# Super-Regenerative-Airband-1Transistor-K.net
KiCad netlist of a schematic drawn in EAGLE
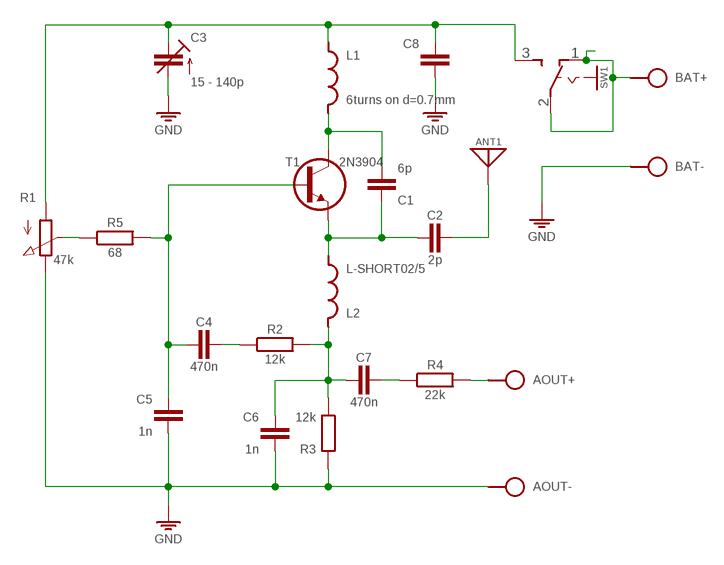
[diagram p0: schematic, sheet 1]

(export (version "E")
  (design (tool "Eeschema 10.0.6"))
  (components
    (comp (ref "ANT1")
      (value "ANT")
      (footprint "eagle-import:SPAD")
      (libsource (lib "eagle-import") (part "ANT"))
    )
    (comp (ref "AOUT+")
      (value "SPAD")
      (footprint "eagle-import:SPAD")
      (libsource (lib "eagle-import") (part "SPAD"))
    )
    (comp (ref "AOUT-")
      (value "SPAD")
      (footprint "eagle-import:SPAD")
      (libsource (lib "eagle-import") (part "SPAD"))
    )
    (comp (ref "BAT+")
      (value "SPAD")
      (footprint "eagle-import:SPAD")
      (libsource (lib "eagle-import") (part "SPAD"))
    )
    (comp (ref "BAT-")
      (value "SPAD")
      (footprint "eagle-import:SPAD")
      (libsource (lib "eagle-import") (part "SPAD"))
    )
    (comp (ref "C1")
      (value "6p")
      (footprint "eagle-import:C050-020X036")
      (libsource (lib "eagle-import") (part "C050-020X036"))
    )
    (comp (ref "C2")
      (value "2p")
      (footprint "eagle-import:C025-015X024")
      (libsource (lib "eagle-import") (part "C025-015X024"))
    )
    (comp (ref "C3")
      (value "15 - 140p")
      (footprint "eagle-import:TRIM-2222-808")
      (libsource (lib "eagle-import") (part "C-TR-PH201272222-808-2PINB"))
    )
    (comp (ref "C4")
      (value "470n")
      (footprint "eagle-import:C050-020X036")
      (libsource (lib "eagle-import") (part "C050-020X036"))
    )
    (comp (ref "C5")
      (value "1n")
      (footprint "eagle-import:C025-020X036")
      (libsource (lib "eagle-import") (part "C025-020X036"))
    )
    (comp (ref "C6")
      (value "1n")
      (footprint "eagle-import:C050-020X036")
      (libsource (lib "eagle-import") (part "C050-020X036"))
    )
    (comp (ref "C7")
      (value "470n")
      (footprint "eagle-import:C050-020X036")
      (libsource (lib "eagle-import") (part "C050-020X036"))
    )
    (comp (ref "C8")
      (value "C050-025X075")
      (footprint "eagle-import:C050-025X075")
      (libsource (lib "eagle-import") (part "C050-025X075"))
    )
    (comp (ref "L1")
      (value "6turns on d=0.7mm")
      (footprint "eagle-import:L-04_7V-X")
      (libsource (lib "eagle-import") (part "L-SHORTL-04/7V-X"))
    )
    (comp (ref "L2")
      (value "L-SHORT02/5")
      (footprint "eagle-import:L-04-5_5V")
      (libsource (lib "eagle-import") (part "L-SHORT04-5/5V"))
    )
    (comp (ref "R1")
      (value "47k")
      (footprint "eagle-import:POT")
      (libsource (lib "eagle-import") (part "POT"))
    )
    (comp (ref "R2")
      (value "12k")
      (footprint "eagle-import:0202_7")
      (libsource (lib "eagle-import") (part "R-H0202/7"))
    )
    (comp (ref "R3")
      (value "12k")
      (footprint "eagle-import:0202_7")
      (libsource (lib "eagle-import") (part "R0202/7"))
    )
    (comp (ref "R4")
      (value "22k")
      (footprint "eagle-import:0202_7")
      (libsource (lib "eagle-import") (part "R-H0202/7"))
    )
    (comp (ref "R5")
      (value "68")
      (footprint "eagle-import:0202_7")
      (libsource (lib "eagle-import") (part "R-H0202/7"))
    )
    (comp (ref "SW1")
      (value "SL-SW-1P-2T-H")
      (footprint "eagle-import:SLSW-1P2T-H")
      (libsource (lib "eagle-import") (part "SL-SW-1P-2T-H"))
    )
    (comp (ref "T1")
      (value "2N3904")
      (footprint "eagle-import:TO92")
      (libsource (lib "eagle-import") (part "2N3904"))
    )
  )
  (nets
    (net (code "1") (name "GND") (class "Default")
      (node (ref "AOUT-") (pin "1") (pinfunction "P$1_1") (pintype "bidirectional"))
      (node (ref "BAT-") (pin "1") (pinfunction "P$1_1") (pintype "bidirectional"))
      (node (ref "C3") (pin "2") (pinfunction "A_2") (pintype "passive"))
      (node (ref "C5") (pin "2") (pinfunction "2_2") (pintype "passive"))
      (node (ref "C6") (pin "2") (pinfunction "2_2") (pintype "passive"))
      (node (ref "C8") (pin "2") (pinfunction "2_2") (pintype "passive"))
      (node (ref "R1") (pin "3") (pinfunction "E_3") (pintype "passive"))
      (node (ref "R3") (pin "2") (pinfunction "2_2") (pintype "passive"))
    )
    (net (code "2") (name "Net-(ANT1-Pad1)") (class "Default")
      (node (ref "ANT1") (pin "1") (pinfunction "1_1") (pintype "output"))
      (node (ref "C2") (pin "1") (pinfunction "1_1") (pintype "passive"))
    )
    (net (code "3") (name "Net-(AOUT+-P$1)") (class "Default")
      (node (ref "AOUT+") (pin "1") (pinfunction "P$1_1") (pintype "bidirectional"))
      (node (ref "R4") (pin "2") (pinfunction "2_2") (pintype "passive"))
    )
    (net (code "4") (name "Net-(BAT+-P$1)") (class "Default")
      (node (ref "BAT+") (pin "1") (pinfunction "P$1_1") (pintype "bidirectional"))
      (node (ref "SW1") (pin "1") (pinfunction "O_1") (pintype "passive"))
      (node (ref "SW1") (pin "2") (pinfunction "P_2") (pintype "passive"))
    )
    (net (code "5") (name "Net-(C3-E)") (class "Default")
      (node (ref "C3") (pin "3") (pinfunction "E_3") (pintype "passive"))
      (node (ref "C8") (pin "1") (pinfunction "1_1") (pintype "passive"))
      (node (ref "L1") (pin "2") (pinfunction "2_2") (pintype "passive"))
      (node (ref "R1") (pin "1") (pinfunction "A_1") (pintype "passive"))
      (node (ref "SW1") (pin "3") (pinfunction "S_3") (pintype "passive"))
    )
    (net (code "6") (name "Net-(C4-Pad1)") (class "Default")
      (node (ref "C4") (pin "1") (pinfunction "1_1") (pintype "passive"))
      (node (ref "R2") (pin "1") (pinfunction "1_1") (pintype "passive"))
    )
    (net (code "7") (name "Net-(C6-Pad1)") (class "Default")
      (node (ref "C6") (pin "1") (pinfunction "1_1") (pintype "passive"))
      (node (ref "C7") (pin "2") (pinfunction "2_2") (pintype "passive"))
      (node (ref "L2") (pin "2") (pinfunction "2_2") (pintype "passive"))
      (node (ref "R2") (pin "2") (pinfunction "2_2") (pintype "passive"))
      (node (ref "R3") (pin "1") (pinfunction "1_1") (pintype "passive"))
    )
    (net (code "8") (name "Net-(C7-Pad1)") (class "Default")
      (node (ref "C7") (pin "1") (pinfunction "1_1") (pintype "passive"))
      (node (ref "R4") (pin "1") (pinfunction "1_1") (pintype "passive"))
    )
    (net (code "9") (name "Net-(R1-S)") (class "Default")
      (node (ref "R1") (pin "2") (pinfunction "S_2") (pintype "passive"))
      (node (ref "R5") (pin "1") (pinfunction "1_1") (pintype "passive"))
    )
    (net (code "10") (name "Net-(T1-B)") (class "Default")
      (node (ref "C4") (pin "2") (pinfunction "2_2") (pintype "passive"))
      (node (ref "C5") (pin "1") (pinfunction "1_1") (pintype "passive"))
      (node (ref "R5") (pin "2") (pinfunction "2_2") (pintype "passive"))
      (node (ref "T1") (pin "2") (pinfunction "B_2") (pintype "passive"))
    )
    (net (code "11") (name "Net-(T1-C)") (class "Default")
      (node (ref "C1") (pin "2") (pinfunction "2_2") (pintype "passive"))
      (node (ref "L1") (pin "1") (pinfunction "1_1") (pintype "passive"))
      (node (ref "T1") (pin "3") (pinfunction "C_3") (pintype "passive"))
    )
    (net (code "12") (name "Net-(T1-E)") (class "Default")
      (node (ref "C1") (pin "1") (pinfunction "1_1") (pintype "passive"))
      (node (ref "C2") (pin "2") (pinfunction "2_2") (pintype "passive"))
      (node (ref "L2") (pin "1") (pinfunction "1_1") (pintype "passive"))
      (node (ref "T1") (pin "1") (pinfunction "E_1") (pintype "passive"))
    )
  )
)
